# USB_PCIe.net
KiCad netlist of a schematic drawn in Altium Designer
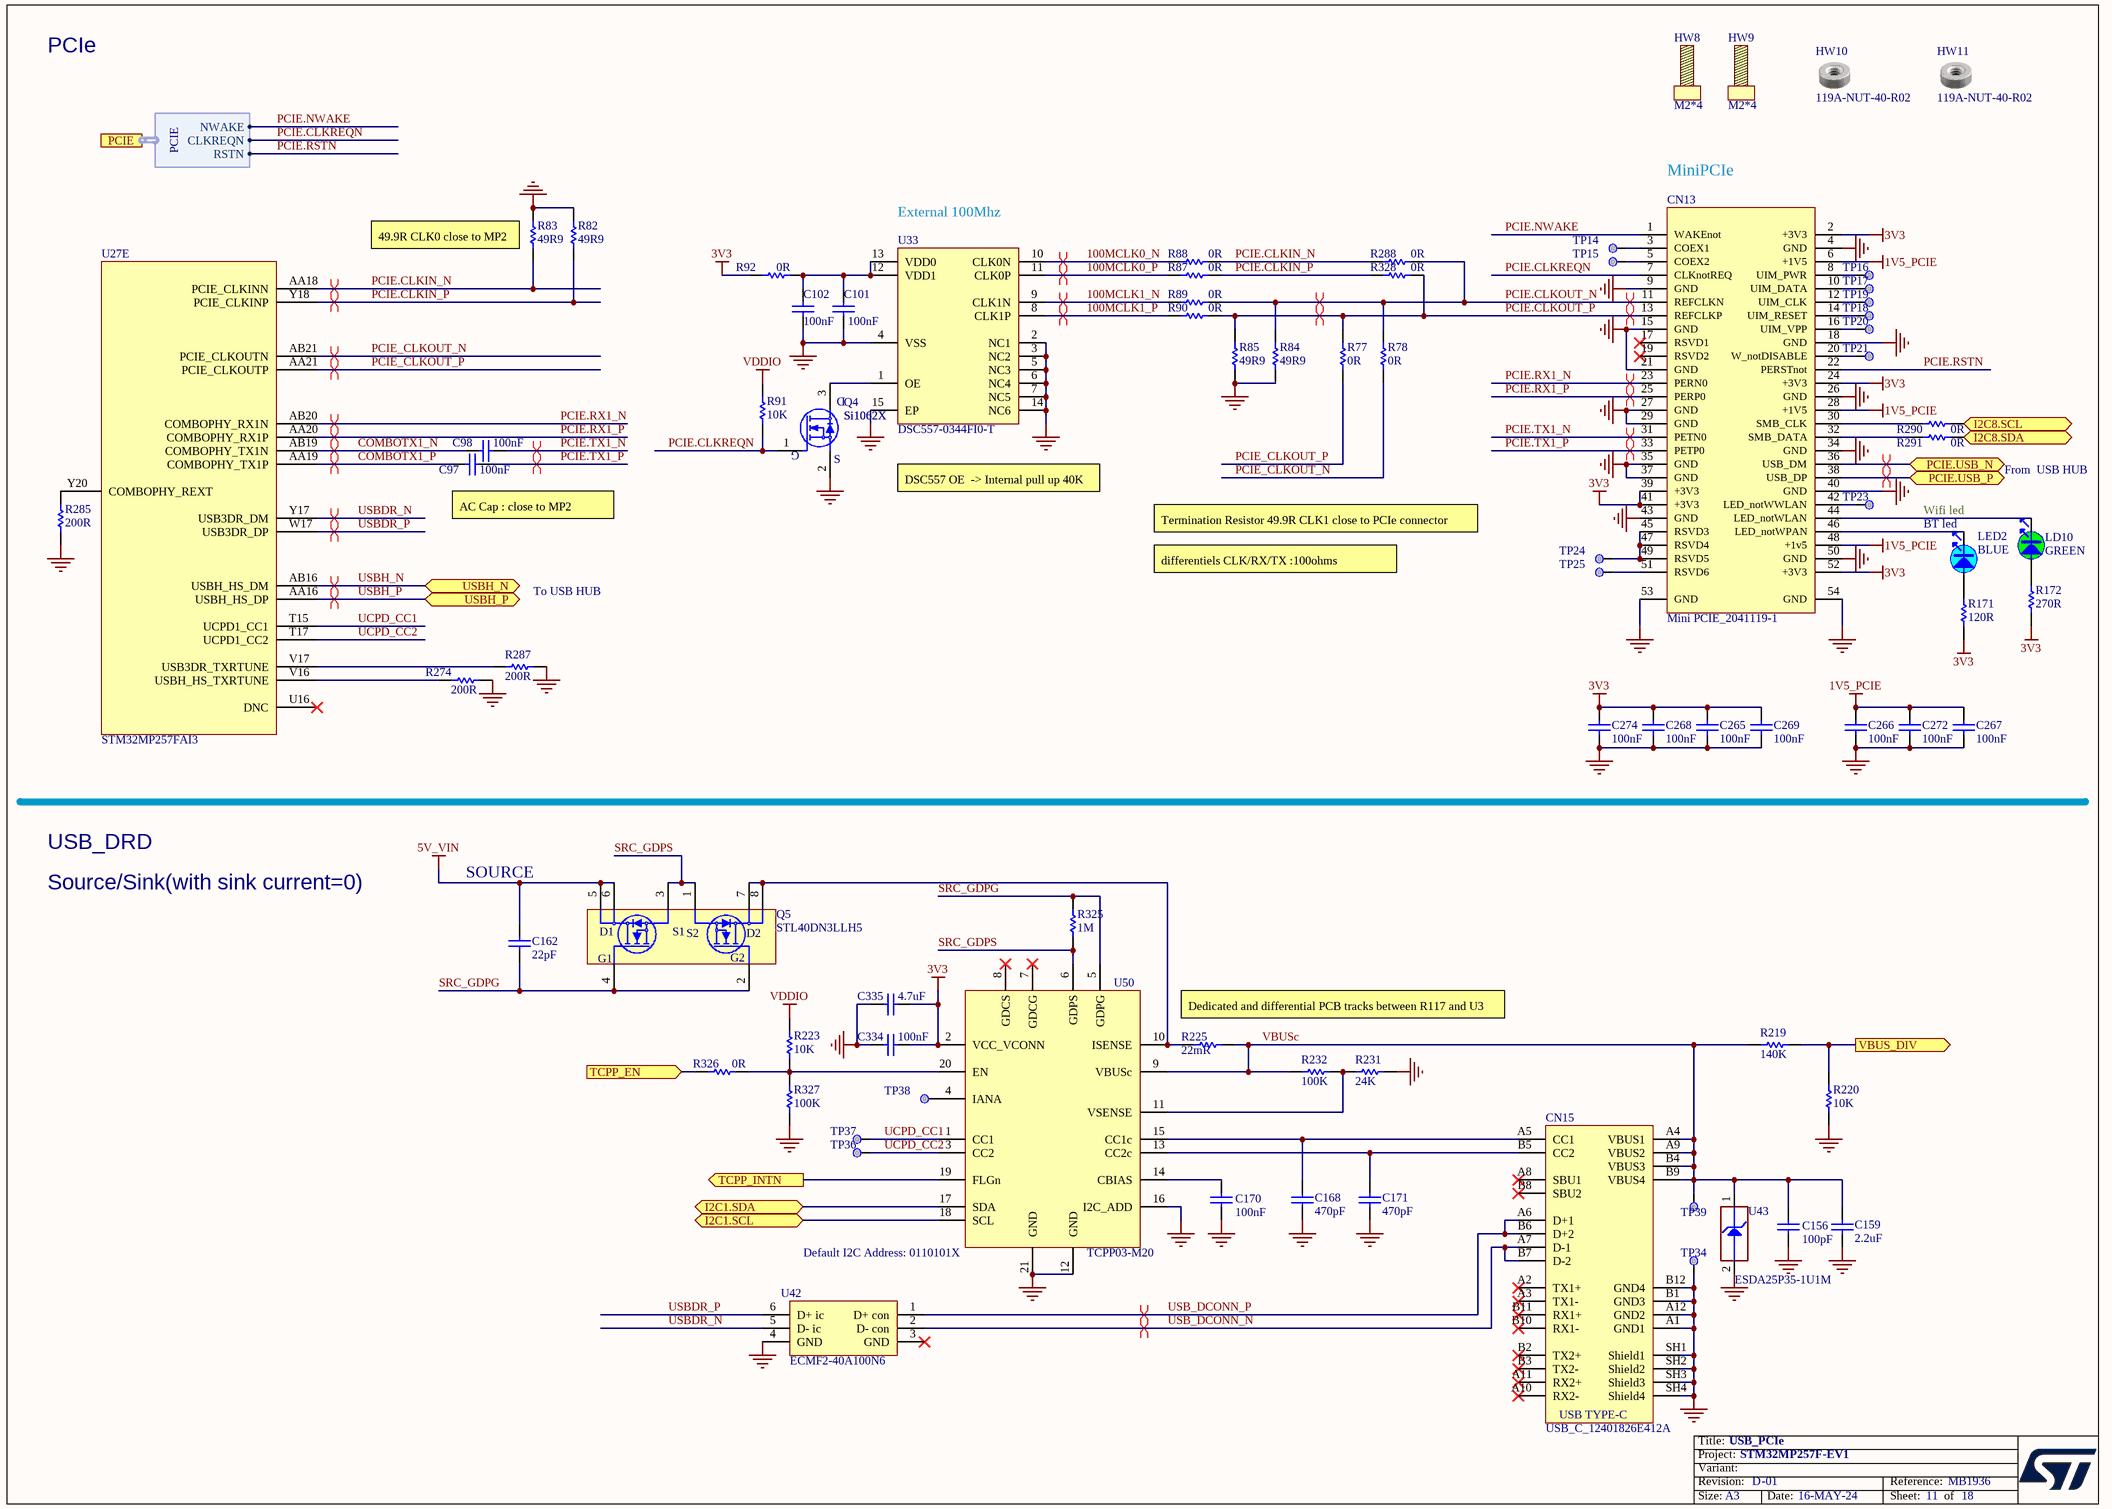
[diagram p0: USB_PCIe.SchDoc]

(export (version "E")
  (design (tool "Eeschema 10.0.6"))
  (components
    (comp (ref "C97")
      (value "100nF")
      (footprint "MCD_PARTS:C0201_MURATA_GRM033_H0P3")
      (description "Capacitor, MLCC,100nF, 10V, X7R, +/-10%, 0201, T=0.3mm")
      (fields (field (name "INTERNAL_PART_NUMBER") "MCD-01535") (field (name "MANUFACTURER") "MURATA"))
      (libsource (lib "MCD_PARTS_database") (part "Capacitor"))
    )
    (comp (ref "C98")
      (value "100nF")
      (footprint "MCD_PARTS:C0201_MURATA_GRM033_H0P3")
      (description "Capacitor, MLCC,100nF, 10V, X7R, +/-10%, 0201, T=0.3mm")
      (fields (field (name "INTERNAL_PART_NUMBER") "MCD-01535") (field (name "MANUFACTURER") "MURATA"))
      (libsource (lib "MCD_PARTS_database") (part "Capacitor"))
    )
    (comp (ref "C101")
      (value "100nF")
      (footprint "MCD_PARTS:C0402")
      (description "Capacitor, MLCC, 100nF, 16V, X7R, +/-10%, 0402, T=0.5mm")
      (fields (field (name "INTERNAL_PART_NUMBER") "MCD-00006") (field (name "MANUFACTURER") "YAGEO"))
      (libsource (lib "MCD_PARTS_database") (part "Capacitor"))
    )
    (comp (ref "C102")
      (value "100nF")
      (footprint "MCD_PARTS:C0402")
      (description "Capacitor, MLCC, 100nF, 16V, X7R, +/-10%, 0402, T=0.5mm")
      (fields (field (name "INTERNAL_PART_NUMBER") "MCD-00006") (field (name "MANUFACTURER") "YAGEO"))
      (libsource (lib "MCD_PARTS_database") (part "Capacitor"))
    )
    (comp (ref "C156")
      (value "100pF")
      (footprint "MCD_PARTS:C0402")
      (description "Capacitor, MLCC, 100pF, 50V, NPO, +/-5%, 0402, T=0.5mm")
      (fields
        (field (name "INTERNAL_PART_NUMBER") "MCD-00205")
        (field (name "MANUFACTURER_PART_NUMBER") "CC0402JRNPO9BN101")
      )
      (libsource (lib "MCD_PARTS_database") (part "Capacitor"))
    )
    (comp (ref "C159")
      (value "2.2uF")
      (footprint "MCD_PARTS:C0805")
      (description "Capacitor, MLCC, 2.2uF, 25V, X7R, +/-10%, 0805, T=1,25mm")
      (fields (field (name "INTERNAL_PART_NUMBER") "MCD-02372") (field (name "MANUFACTURER") "MURATA"))
      (libsource (lib "MCD_PARTS_database") (part "Capacitor"))
    )
    (comp (ref "C162")
      (value "22pF")
      (footprint "MCD_PARTS:C0402")
      (description "Capacitor, MLCC, 22pF, 50V, C0G, +/-5%, 0402, T=0.5mm")
      (fields (field (name "INTERNAL_PART_NUMBER") "MCD-01995") (field (name "MANUFACTURER") "TDK"))
      (libsource (lib "MCD_PARTS_database") (part "Capacitor"))
    )
    (comp (ref "C168")
      (value "470pF")
      (footprint "MCD_PARTS:C0402")
      (description "Capacitor, MLCC, 470pF, 50V, NPO, +/-5%, 0402, T=0.5mm")
      (fields
        (field (name "INTERNAL_PART_NUMBER") "MCD-00724")
        (field (name "MANUFACTURER_PART_NUMBER") "CC0402JRNPO9BN471")
      )
      (libsource (lib "MCD_PARTS_database") (part "Capacitor"))
    )
    (comp (ref "C170")
      (value "100nF")
      (footprint "MCD_PARTS:C0603")
      (description "Capacitor, MLCC, 100nF, 50V, X7R, +/-10%, 0603, T=0.8mm")
      (fields (field (name "INTERNAL_PART_NUMBER") "MCD-01099") (field (name "BMS_PART_NUMBER") "9142278"))
      (libsource (lib "MCD_PARTS_database") (part "Capacitor"))
    )
    (comp (ref "C171")
      (value "470pF")
      (footprint "MCD_PARTS:C0402")
      (description "Capacitor, MLCC, 470pF, 50V, NPO, +/-5%, 0402, T=0.5mm")
      (fields
        (field (name "INTERNAL_PART_NUMBER") "MCD-00724")
        (field (name "MANUFACTURER_PART_NUMBER") "CC0402JRNPO9BN471")
      )
      (libsource (lib "MCD_PARTS_database") (part "Capacitor"))
    )
    (comp (ref "C265")
      (value "100nF")
      (footprint "MCD_PARTS:C0201_H0P3")
      (description "Capacitor, MLCC, 100nF,10V, X5R, +/-10%, 0201, T=0.3mm")
      (fields
        (field (name "INTERNAL_PART_NUMBER") "MCD-00697")
        (field (name "MANUFACTURER_PART_NUMBER") "C0603X5R1A104K030BC")
      )
      (libsource (lib "MCD_PARTS_database") (part "Capacitor"))
    )
    (comp (ref "C266")
      (value "100nF")
      (footprint "MCD_PARTS:C0201_H0P3")
      (description "Capacitor, MLCC, 100nF,10V, X5R, +/-10%, 0201, T=0.3mm")
      (fields
        (field (name "INTERNAL_PART_NUMBER") "MCD-00697")
        (field (name "MANUFACTURER_PART_NUMBER") "C0603X5R1A104K030BC")
      )
      (libsource (lib "MCD_PARTS_database") (part "Capacitor"))
    )
    (comp (ref "C267")
      (value "100nF")
      (footprint "MCD_PARTS:C0201_H0P3")
      (description "Capacitor, MLCC, 100nF,10V, X5R, +/-10%, 0201, T=0.3mm")
      (fields
        (field (name "INTERNAL_PART_NUMBER") "MCD-00697")
        (field (name "MANUFACTURER_PART_NUMBER") "C0603X5R1A104K030BC")
      )
      (libsource (lib "MCD_PARTS_database") (part "Capacitor"))
    )
    (comp (ref "C268")
      (value "100nF")
      (footprint "MCD_PARTS:C0201_H0P3")
      (description "Capacitor, MLCC, 100nF,10V, X5R, +/-10%, 0201, T=0.3mm")
      (fields
        (field (name "INTERNAL_PART_NUMBER") "MCD-00697")
        (field (name "MANUFACTURER_PART_NUMBER") "C0603X5R1A104K030BC")
      )
      (libsource (lib "MCD_PARTS_database") (part "Capacitor"))
    )
    (comp (ref "C269")
      (value "100nF")
      (footprint "MCD_PARTS:C0201_H0P3")
      (description "Capacitor, MLCC, 100nF,10V, X5R, +/-10%, 0201, T=0.3mm")
      (fields
        (field (name "INTERNAL_PART_NUMBER") "MCD-00697")
        (field (name "MANUFACTURER_PART_NUMBER") "C0603X5R1A104K030BC")
      )
      (libsource (lib "MCD_PARTS_database") (part "Capacitor"))
    )
    (comp (ref "C272")
      (value "100nF")
      (footprint "MCD_PARTS:C0201_H0P3")
      (description "Capacitor, MLCC, 100nF,10V, X5R, +/-10%, 0201, T=0.3mm")
      (fields
        (field (name "INTERNAL_PART_NUMBER") "MCD-00697")
        (field (name "MANUFACTURER_PART_NUMBER") "C0603X5R1A104K030BC")
      )
      (libsource (lib "MCD_PARTS_database") (part "Capacitor"))
    )
    (comp (ref "C274")
      (value "100nF")
      (footprint "MCD_PARTS:C0201_H0P3")
      (description "Capacitor, MLCC, 100nF,10V, X5R, +/-10%, 0201, T=0.3mm")
      (fields
        (field (name "INTERNAL_PART_NUMBER") "MCD-00697")
        (field (name "MANUFACTURER_PART_NUMBER") "C0603X5R1A104K030BC")
      )
      (libsource (lib "MCD_PARTS_database") (part "Capacitor"))
    )
    (comp (ref "C334")
      (value "100nF")
      (footprint "MCD_PARTS:C0402")
      (description "Capacitor, MLCC, 100nF, 16V, X7R, +/-10%, 0402, T=0.5mm")
      (fields (field (name "INTERNAL_PART_NUMBER") "MCD-00006") (field (name "MANUFACTURER") "YAGEO"))
      (libsource (lib "MCD_PARTS_database") (part "Capacitor"))
    )
    (comp (ref "C335")
      (value "4.7uF")
      (footprint "MCD_PARTS:C0402")
      (description "Capacitor, MLCC, 4.7uF, 6V3, X5R, +/-20%, 0402, T=0.5mm")
      (fields (field (name "INTERNAL_PART_NUMBER") "MCD-01356") (field (name "MANUFACTURER") "MURATA"))
      (libsource (lib "MCD_PARTS_database") (part "Capacitor"))
    )
    (comp (ref "CN13")
      (value "Mini PCIE_2041119-1")
      (footprint "MCD_PARTS:CON_TE-CONNECTIVITY_2041119-1_HALF-CARD")
      (description "Socket_Mini PCIE, 52 pins, RA, SMD, T=4mm")
      (fields
        (field (name "INTERNAL_PART_NUMBER") "MCD-02227")
        (field (name "MANUFACTURER") "TE CONNECTIVITY")
      )
      (libsource (lib "MCD_PARTS_database") (part "SOCKET_Mini_PCIE"))
    )
    (comp (ref "CN15")
      (value "USB_C_12401826E412A")
      (footprint "MCD_PARTS:CON_USB-TYPEC_AMPHENOL_12401826E412A")
      (description "USB_TypeC, 24 pins, RA, SMD, T=2.96mm")
      (fields (field (name "INTERNAL_PART_NUMBER") "MCD-03232") (field (name "MANUFACTURER") "AMPHENOL ICC"))
      (libsource (lib "MCD_PARTS_database") (part "USB_TYPE_C_Receptacle"))
    )
    (comp (ref "HW8")
      (value "M2*4")
      (description "Screw , M2*4 mm")
      (fields (field (name "INTERNAL_PART_NUMBER") "MCD-02934") (field (name "MANUFACTURER") "RS PRO"))
      (libsource (lib "MCD_PARTS_database") (part "SCREW"))
    )
    (comp (ref "HW9")
      (value "M2*4")
      (description "Screw , M2*4 mm")
      (fields (field (name "INTERNAL_PART_NUMBER") "MCD-02934") (field (name "MANUFACTURER") "RS PRO"))
      (libsource (lib "MCD_PARTS_database") (part "SCREW"))
    )
    (comp (ref "HW10")
      (value "119A-NUT-40-R02")
      (footprint "MCD_PARTS:MISC_119A-NUT-40-R02")
      (description "MiniPCIe Stand off , 1.6mm")
      (fields (field (name "INTERNAL_PART_NUMBER") "MCD-03022") (field (name "MANUFACTURER") "ATTEND"))
      (libsource (lib "MCD_PARTS_database") (part "Standoff_mini_PCIE"))
    )
    (comp (ref "HW11")
      (value "119A-NUT-40-R02")
      (footprint "MCD_PARTS:MISC_119A-NUT-40-R02")
      (description "MiniPCIe Stand off , 1.6mm")
      (fields (field (name "INTERNAL_PART_NUMBER") "MCD-03022") (field (name "MANUFACTURER") "ATTEND"))
      (libsource (lib "MCD_PARTS_database") (part "Standoff_mini_PCIE"))
    )
    (comp (ref "LD10")
      (value "GREEN")
      (footprint "MCD_PARTS:LED_0603_OSRAM_LG-Q396-PS-35_GREEN_1A2K_H0P4")
      (description "LED Green, 0603 SMD, Forward Voltage Typ=2V, Max=2.5V")
      (fields
        (field (name "INTERNAL_PART_NUMBER") "MCD-00588")
        (field (name "MANUFACTURER_PART_NUMBER") "LG Q396-PS-35")
        (field (name "PROVIDED_BY") "SUBCO")
      )
      (libsource (lib "MCD_PARTS_database") (part "LED_green"))
    )
    (comp (ref "LED2")
      (value "BLUE")
      (footprint "MCD_PARTS:LED_0603_OSRAM_LB-Q39G-L2OO-35-1_BLUE_1A2K_H0P4")
      (description "LED Blue, 0603 SMD, Forward Voltage Min=2,8V, Max=3,8V")
      (fields
        (field (name "INTERNAL_PART_NUMBER") "MCD-00585")
        (field (name "MANUFACTURER_PART_NUMBER") "LB Q39G-L2OO-35-1")
        (field (name "PROVIDED_BY") "SUBCO")
      )
      (libsource (lib "MCD_PARTS_database") (part "LED_blue"))
    )
    (comp (ref "Q4")
      (value "Si1062X")
      (footprint "MCD_PARTS:MOS_SC89-3L")
      (description "MOSFET N-CH 20V SC-89")
      (fields
        (field (name "INTERNAL_PART_NUMBER") "MCD-02221")
        (field (name "MANUFACTURER") "VISHAY")
        (field (name "MANUFACTURER_PART_NUMBER") "Si1062X")
      )
      (libsource (lib "MCD_PARTS_database") (part "MOSFET_N-CHANNEL"))
    )
    (comp (ref "Q5")
      (value "STL40DN3LLH5")
      (footprint "MCD_PARTS:PowerFLAT_5x6")
      (description "MOSFET, Dual N-channel 30 V, 0.016 Ω typ., 40 A, STripFET™ H5 Power MOSFET")
      (fields
        (field (name "INTERNAL_PART_NUMBER") "MCD-02152")
        (field (name "MANUFACTURER") "STMICROELECTRONICS")
      )
      (libsource (lib "MCD_PARTS_database") (part "STL40DN3LLH5"))
    )
    (comp (ref "R77")
      (value "0R")
      (footprint "MCD_PARTS:R0402")
      (description "Resistor, 0R, 0402, +/-5%, 1/16W")
      (fields (field (name "INTERNAL_PART_NUMBER") "MCD-00052") (field (name "MANUFACTURER") "YAGEO"))
      (libsource (lib "MCD_PARTS_database") (part "Resistor"))
    )
    (comp (ref "R78")
      (value "0R")
      (footprint "MCD_PARTS:R0402")
      (description "Resistor, 0R, 0402, +/-5%, 1/16W")
      (fields (field (name "INTERNAL_PART_NUMBER") "MCD-00052") (field (name "MANUFACTURER") "YAGEO"))
      (libsource (lib "MCD_PARTS_database") (part "Resistor"))
    )
    (comp (ref "R82")
      (value "49R9")
      (footprint "MCD_PARTS:R0402")
      (description "Resistor, 49R9, 0402, +/-1%, 1/16W")
      (fields (field (name "INTERNAL_PART_NUMBER") "MCD-00565") (field (name "MANUFACTURER") "YAGEO"))
      (libsource (lib "MCD_PARTS_database") (part "Resistor"))
    )
    (comp (ref "R83")
      (value "49R9")
      (footprint "MCD_PARTS:R0402")
      (description "Resistor, 49R9, 0402, +/-1%, 1/16W")
      (fields (field (name "INTERNAL_PART_NUMBER") "MCD-00565") (field (name "MANUFACTURER") "YAGEO"))
      (libsource (lib "MCD_PARTS_database") (part "Resistor"))
    )
    (comp (ref "R84")
      (value "49R9")
      (footprint "MCD_PARTS:R0402")
      (description "Resistor, 49R9, 0402, +/-1%, 1/16W")
      (fields (field (name "INTERNAL_PART_NUMBER") "MCD-00565") (field (name "MANUFACTURER") "YAGEO"))
      (libsource (lib "MCD_PARTS_database") (part "Resistor"))
    )
    (comp (ref "R85")
      (value "49R9")
      (footprint "MCD_PARTS:R0402")
      (description "Resistor, 49R9, 0402, +/-1%, 1/16W")
      (fields (field (name "INTERNAL_PART_NUMBER") "MCD-00565") (field (name "MANUFACTURER") "YAGEO"))
      (libsource (lib "MCD_PARTS_database") (part "Resistor"))
    )
    (comp (ref "R87")
      (value "0R")
      (footprint "MCD_PARTS:R0402")
      (description "Resistor, 0R, 0402, +/-5%, 1/16W")
      (fields (field (name "INTERNAL_PART_NUMBER") "MCD-00052") (field (name "MANUFACTURER") "YAGEO"))
      (libsource (lib "MCD_PARTS_database") (part "Resistor"))
    )
    (comp (ref "R88")
      (value "0R")
      (footprint "MCD_PARTS:R0402")
      (description "Resistor, 0R, 0402, +/-5%, 1/16W")
      (fields (field (name "INTERNAL_PART_NUMBER") "MCD-00052") (field (name "MANUFACTURER") "YAGEO"))
      (libsource (lib "MCD_PARTS_database") (part "Resistor"))
    )
    (comp (ref "R89")
      (value "0R")
      (footprint "MCD_PARTS:R0402")
      (description "Resistor, 0R, 0402, +/-5%, 1/16W")
      (fields (field (name "INTERNAL_PART_NUMBER") "MCD-00052") (field (name "MANUFACTURER") "YAGEO"))
      (libsource (lib "MCD_PARTS_database") (part "Resistor"))
    )
    (comp (ref "R90")
      (value "0R")
      (footprint "MCD_PARTS:R0402")
      (description "Resistor, 0R, 0402, +/-5%, 1/16W")
      (fields (field (name "INTERNAL_PART_NUMBER") "MCD-00052") (field (name "MANUFACTURER") "YAGEO"))
      (libsource (lib "MCD_PARTS_database") (part "Resistor"))
    )
    (comp (ref "R91")
      (value "10K")
      (footprint "MCD_PARTS:R0402")
      (description "Resistor, 10K, 0402, +/-1%, 1/16W")
      (fields (field (name "INTERNAL_PART_NUMBER") "MCD-00053") (field (name "BMS_PART_NUMBER") "9131590"))
      (libsource (lib "MCD_PARTS_database") (part "Resistor"))
    )
    (comp (ref "R92")
      (value "0R")
      (footprint "MCD_PARTS:R0402")
      (description "Resistor, 0R, 0402, +/-5%, 1/16W")
      (fields (field (name "INTERNAL_PART_NUMBER") "MCD-00052") (field (name "MANUFACTURER") "YAGEO"))
      (libsource (lib "MCD_PARTS_database") (part "Resistor"))
    )
    (comp (ref "R171")
      (value "120R")
      (footprint "MCD_PARTS:R0402")
      (description "Resistor,120R,0402,1%,1/16W")
      (fields
        (field (name "INTERNAL_PART_NUMBER") "MCD-00194")
        (field (name "MANUFACTURER_PART_NUMBER") "RC0402FR-07120RL")
        (field (name "PROVIDED_BY") "SUBCO")
      )
      (libsource (lib "MCD_PARTS_database") (part "Resistor"))
    )
    (comp (ref "R172")
      (value "270R")
      (footprint "MCD_PARTS:R0402")
      (description "Resistor,270R,0402,1%,1/16W")
      (fields
        (field (name "INTERNAL_PART_NUMBER") "MCD-00441")
        (field (name "MANUFACTURER_PART_NUMBER") "RC0402FR-07270RL")
        (field (name "PROVIDED_BY") "SUBCO")
      )
      (libsource (lib "MCD_PARTS_database") (part "Resistor"))
    )
    (comp (ref "R219")
      (value "140K")
      (footprint "MCD_PARTS:R0402")
      (description "Resistor, 140K, 0402, +/-1%, 1/16W")
      (fields (field (name "INTERNAL_PART_NUMBER") "MCD-02335") (field (name "MANUFACTURER") "YAGEO"))
      (libsource (lib "MCD_PARTS_database") (part "Resistor"))
    )
    (comp (ref "R220")
      (value "10K")
      (footprint "MCD_PARTS:R0402")
      (description "Resistor, 10K, 0402, +/-1%, 1/16W")
      (fields (field (name "INTERNAL_PART_NUMBER") "MCD-00053") (field (name "BMS_PART_NUMBER") "9131590"))
      (libsource (lib "MCD_PARTS_database") (part "Resistor"))
    )
    (comp (ref "R223")
      (value "10K")
      (footprint "MCD_PARTS:R0402")
      (description "Resistor, 10K, 0402, +/-1%, 1/16W")
      (fields (field (name "INTERNAL_PART_NUMBER") "MCD-00053") (field (name "BMS_PART_NUMBER") "9131590"))
      (libsource (lib "MCD_PARTS_database") (part "Resistor"))
    )
    (comp (ref "R225")
      (value "22mR")
      (footprint "MCD_PARTS:R0603")
      (description "Resistor, 22mR, 0603, +/-1%, 1/3W")
      (fields (field (name "INTERNAL_PART_NUMBER") "MCD-02232") (field (name "MANUFACTURER") "PANASONIC"))
      (libsource (lib "MCD_PARTS_database") (part "Resistor"))
    )
    (comp (ref "R231")
      (value "24K")
      (footprint "MCD_PARTS:R0402")
      (description "Resistor, 24K, 0402, +/-1%, 1/16W")
      (fields (field (name "INTERNAL_PART_NUMBER") "MCD-00435") (field (name "MANUFACTURER") "YAGEO"))
      (libsource (lib "MCD_PARTS_database") (part "Resistor"))
    )
    (comp (ref "R232")
      (value "100K")
      (footprint "MCD_PARTS:R0402")
      (description "Resistor,100K,0402,0.5%,1/16W")
      (fields (field (name "INTERNAL_PART_NUMBER") "MCD-02265") (field (name "MANUFACTURER") "YAGEO"))
      (libsource (lib "MCD_PARTS_database") (part "Resistor"))
    )
    (comp (ref "R274")
      (value "200R")
      (footprint "MCD_PARTS:R0402")
      (description "Resistor, 200R, 0402, +/-1%, 1/16W")
      (fields (field (name "INTERNAL_PART_NUMBER") "MCD-00417") (field (name "MANUFACTURER") "YAGEO"))
      (libsource (lib "MCD_PARTS_database") (part "Resistor"))
    )
    (comp (ref "R285")
      (value "200R")
      (footprint "MCD_PARTS:R0402")
      (description "Resistor, 200R, 0402, +/-1%, 1/16W")
      (fields (field (name "INTERNAL_PART_NUMBER") "MCD-00417") (field (name "MANUFACTURER") "YAGEO"))
      (libsource (lib "MCD_PARTS_database") (part "Resistor"))
    )
    (comp (ref "R287")
      (value "200R")
      (footprint "MCD_PARTS:R0402")
      (description "Resistor, 200R, 0402, +/-1%, 1/16W")
      (fields (field (name "INTERNAL_PART_NUMBER") "MCD-00417") (field (name "MANUFACTURER") "YAGEO"))
      (libsource (lib "MCD_PARTS_database") (part "Resistor"))
    )
    (comp (ref "R288")
      (value "0R")
      (footprint "MCD_PARTS:R0402")
      (description "Resistor,0R,0402,5%,1/16W")
      (fields (field (name "INTERNAL_PART_NUMBER") "MCD-00052") (field (name "MANUFACTURER") "YAGEO"))
      (libsource (lib "MCD_PARTS_database") (part "Resistor"))
    )
    (comp (ref "R290")
      (value "0R")
      (footprint "MCD_PARTS:R0402")
      (description "Resistor, 0R, 0402, +/-5%, 1/16W")
      (fields (field (name "INTERNAL_PART_NUMBER") "MCD-00052") (field (name "MANUFACTURER") "YAGEO"))
      (libsource (lib "MCD_PARTS_database") (part "Resistor"))
    )
    (comp (ref "R291")
      (value "0R")
      (footprint "MCD_PARTS:R0402")
      (description "Resistor, 0R, 0402, +/-5%, 1/16W")
      (fields (field (name "INTERNAL_PART_NUMBER") "MCD-00052") (field (name "MANUFACTURER") "YAGEO"))
      (libsource (lib "MCD_PARTS_database") (part "Resistor"))
    )
    (comp (ref "R325")
      (value "1M")
      (footprint "MCD_PARTS:R0402")
      (description "Resistor, 1M, 0402, +/-1%, 1/16W")
      (fields (field (name "INTERNAL_PART_NUMBER") "MCD-00182") (field (name "BMS_PART_NUMBER") "9131778"))
      (libsource (lib "MCD_PARTS_database") (part "Resistor"))
    )
    (comp (ref "R326")
      (value "0R")
      (footprint "MCD_PARTS:R0402")
      (description "Resistor,0R,0402,5%,1/16W")
      (fields
        (field (name "INTERNAL_PART_NUMBER") "MCD-00052")
        (field (name "MANUFACTURER_PART_NUMBER") "RC0402JR-070RL")
      )
      (libsource (lib "MCD_PARTS_database") (part "Resistor"))
    )
    (comp (ref "R327")
      (value "100K")
      (footprint "MCD_PARTS:R0402")
      (description "Resistor,100K,0402,0.5%,1/16W")
      (fields (field (name "INTERNAL_PART_NUMBER") "MCD-02265") (field (name "MANUFACTURER") "YAGEO"))
      (libsource (lib "MCD_PARTS_database") (part "Resistor"))
    )
    (comp (ref "R328")
      (value "0R")
      (footprint "MCD_PARTS:R0402")
      (description "Resistor,0R,0402,5%,1/16W")
      (fields (field (name "INTERNAL_PART_NUMBER") "MCD-00052") (field (name "MANUFACTURER") "YAGEO"))
      (libsource (lib "MCD_PARTS_database") (part "Resistor"))
    )
    (comp (ref "TP14")
      (value "Test Point")
      (footprint "MCD_PARTS:TP_SMD_1MM")
      (description "Test Point 1mm")
      (fields
        (field (name "INTERNAL_PART_NUMBER") "MCD-00074")
        (field (name "MANUFACTURER_PART_NUMBER") "n/a")
      )
      (libsource (lib "") (part "Test Point_1"))
    )
    (comp (ref "TP15")
      (value "Test Point")
      (footprint "MCD_PARTS:TP_SMD_1MM")
      (description "Test Point 1mm")
      (fields
        (field (name "INTERNAL_PART_NUMBER") "MCD-00074")
        (field (name "MANUFACTURER_PART_NUMBER") "n/a")
      )
      (libsource (lib "") (part "Test Point_1"))
    )
    (comp (ref "TP16")
      (value "Test Point")
      (footprint "MCD_PARTS:TP_SMD_1MM")
      (description "Test Point 1mm")
      (fields
        (field (name "INTERNAL_PART_NUMBER") "MCD-00074")
        (field (name "MANUFACTURER_PART_NUMBER") "n/a")
      )
      (libsource (lib "MCD_PARTS_database") (part "Test Point"))
    )
    (comp (ref "TP17")
      (value "Test Point")
      (footprint "MCD_PARTS:TP_SMD_1MM")
      (description "Test Point 1mm")
      (fields
        (field (name "INTERNAL_PART_NUMBER") "MCD-00074")
        (field (name "MANUFACTURER_PART_NUMBER") "n/a")
      )
      (libsource (lib "MCD_PARTS_database") (part "Test Point"))
    )
    (comp (ref "TP18")
      (value "Test Point")
      (footprint "MCD_PARTS:TP_SMD_1MM")
      (description "Test Point 1mm")
      (fields
        (field (name "INTERNAL_PART_NUMBER") "MCD-00074")
        (field (name "MANUFACTURER_PART_NUMBER") "n/a")
      )
      (libsource (lib "MCD_PARTS_database") (part "Test Point"))
    )
    (comp (ref "TP19")
      (value "Test Point")
      (footprint "MCD_PARTS:TP_SMD_1MM")
      (description "Test Point 1mm")
      (fields
        (field (name "INTERNAL_PART_NUMBER") "MCD-00074")
        (field (name "MANUFACTURER_PART_NUMBER") "n/a")
      )
      (libsource (lib "MCD_PARTS_database") (part "Test Point"))
    )
    (comp (ref "TP20")
      (value "Test Point")
      (footprint "MCD_PARTS:TP_SMD_1MM")
      (description "Test Point 1mm")
      (fields
        (field (name "INTERNAL_PART_NUMBER") "MCD-00074")
        (field (name "MANUFACTURER_PART_NUMBER") "n/a")
      )
      (libsource (lib "MCD_PARTS_database") (part "Test Point"))
    )
    (comp (ref "TP21")
      (value "Test Point")
      (footprint "MCD_PARTS:TP_SMD_1MM")
      (description "Test Point 1mm")
      (fields
        (field (name "INTERNAL_PART_NUMBER") "MCD-00074")
        (field (name "MANUFACTURER_PART_NUMBER") "n/a")
      )
      (libsource (lib "MCD_PARTS_database") (part "Test Point"))
    )
    (comp (ref "TP23")
      (value "Test Point")
      (footprint "MCD_PARTS:TP_SMD_1MM")
      (description "Test Point 1mm")
      (fields
        (field (name "INTERNAL_PART_NUMBER") "MCD-00074")
        (field (name "MANUFACTURER_PART_NUMBER") "n/a")
      )
      (libsource (lib "MCD_PARTS_database") (part "Test Point"))
    )
    (comp (ref "TP24")
      (value "Test Point")
      (footprint "MCD_PARTS:TP_SMD_1MM")
      (description "Test Point 1mm")
      (fields
        (field (name "INTERNAL_PART_NUMBER") "MCD-00074")
        (field (name "MANUFACTURER_PART_NUMBER") "n/a")
      )
      (libsource (lib "") (part "Test Point_1"))
    )
    (comp (ref "TP25")
      (value "Test Point")
      (footprint "MCD_PARTS:TP_SMD_1MM")
      (description "Test Point 1mm")
      (fields
        (field (name "INTERNAL_PART_NUMBER") "MCD-00074")
        (field (name "MANUFACTURER_PART_NUMBER") "n/a")
      )
      (libsource (lib "") (part "Test Point_1"))
    )
    (comp (ref "TP34")
      (value "Test Point")
      (footprint "MCD_PARTS:TP_SMD_1MM")
      (description "Test Point 1mm")
      (fields
        (field (name "INTERNAL_PART_NUMBER") "MCD-00074")
        (field (name "MANUFACTURER_PART_NUMBER") "n/a")
      )
      (libsource (lib "") (part "Test Point_2"))
    )
    (comp (ref "TP36")
      (value "Test Point")
      (footprint "MCD_PARTS:TP_SMD_1MM")
      (description "Test Point 1mm")
      (fields
        (field (name "INTERNAL_PART_NUMBER") "MCD-00074")
        (field (name "MANUFACTURER_PART_NUMBER") "n/a")
      )
      (libsource (lib "") (part "Test Point_1"))
    )
    (comp (ref "TP37")
      (value "Test Point")
      (footprint "MCD_PARTS:TP_SMD_1MM")
      (description "Test Point 1mm")
      (fields
        (field (name "INTERNAL_PART_NUMBER") "MCD-00074")
        (field (name "MANUFACTURER_PART_NUMBER") "n/a")
      )
      (libsource (lib "") (part "Test Point_1"))
    )
    (comp (ref "TP38")
      (value "Test Point")
      (footprint "MCD_PARTS:TP_SMD_1MM")
      (description "Test Point 1mm")
      (fields
        (field (name "INTERNAL_PART_NUMBER") "MCD-00074")
        (field (name "MANUFACTURER_PART_NUMBER") "n/a")
      )
      (libsource (lib "") (part "Test Point_1"))
    )
    (comp (ref "TP39")
      (value "Test Point")
      (footprint "MCD_PARTS:TP_SMD_1MM")
      (description "Test Point 1mm")
      (fields
        (field (name "INTERNAL_PART_NUMBER") "MCD-00074")
        (field (name "MANUFACTURER_PART_NUMBER") "n/a")
      )
      (libsource (lib "") (part "Test Point_3"))
    )
    (comp (ref "U27")
      (value "STM32MP257FAI3")
      (footprint "ICC_LFBGA436_18X18_P080_H1P70_STM32MP257_CODE-B0D1")
      (description "MPU, ARM Cortex-A35 + M33 32-bit MPU, 808KB RAM, With Crypto")
      (fields
        (field (name "INTERNAL_PART_NUMBER") "MCD-02000")
        (field (name "MANUFACTURER") "STMICROELECTRONICS")
      )
      (libsource (lib "MCD_PARTS_database") (part "STM32MP257FAI3"))
    )
    (comp (ref "U33")
      (value "DSC557-0344FI0-T")
      (footprint "MCD_PARTS:ICC_QFN14-EPAD_3P2X2P5_P050")
      (description "Crystal-less Two Output PCIe Gen1/2/3 Clock Generator 100Mhz , 2.25V to 3.6V, 100ppm")
      (fields (field (name "INTERNAL_PART_NUMBER") "MCD-02349") (field (name "MANUFACTURER") "MICROCHIP"))
      (libsource (lib "MCD_PARTS_database") (part "DSC557-0344FI0-T"))
    )
    (comp (ref "U42")
      (value "ECMF2-40A100N6")
      (footprint "MCD_PARTS:ESD_UQFN-6L_1P45X1P4_P040")
      (description "ESD protection & Common Filter High Speed serial Interfaces , 0.4 pitch")
      (fields
        (field (name "INTERNAL_PART_NUMBER") "MCD-03060")
        (field (name "MANUFACTURER") "STMICROELECTRONICS")
      )
      (libsource (lib "MCD_PARTS_database") (part "ECMF2-40A100N6"))
    )
    (comp (ref "U43")
      (value "ESDA25P35-1U1M")
      (footprint "MCD_PARTS:ESD_QFN1610_2N_1K_2A")
      (description "High power Transient voltage suppressor:25V/35A EOS and ESD transients protection.")
      (fields (field (name "INTERNAL_PART_NUMBER") "MCD-01207") (field (name "BMS_PART_NUMBER") "9179045"))
      (libsource (lib "MCD_PARTS_database") (part "ESD-TRANSIL"))
    )
    (comp (ref "U50")
      (value "TCPP03-M20")
      (footprint "MCD_PARTS:ICC_QFN20-EPAD_4X4_P050")
      (description "USB Type-C Port Protection for USB DRP Power Delivery, PPS compliant")
      (fields
        (field (name "INTERNAL_PART_NUMBER") "MCD-02130")
        (field (name "MANUFACTURER") "STMICROELECTRONICS")
      )
      (libsource (lib "MCD_PARTS_database") (part "TCPP03-M20"))
    )
  )
  (nets
    (net (code "2") (name "/100MCLK0_N") (class "Default")
      (node (ref "R88") (pin "1") (pinfunction "1_1") (pintype "passive"))
      (node (ref "U33") (pin "10") (pinfunction "CLK0N_10") (pintype "passive"))
    )
    (net (code "3") (name "/100MCLK0_P") (class "Default")
      (node (ref "R87") (pin "1") (pinfunction "1_1") (pintype "passive"))
      (node (ref "U33") (pin "11") (pinfunction "CLK0P_11") (pintype "passive"))
    )
    (net (code "4") (name "/100MCLK1_N") (class "Default")
      (node (ref "R89") (pin "1") (pinfunction "1_1") (pintype "passive"))
      (node (ref "U33") (pin "9") (pinfunction "CLK1N_9") (pintype "passive"))
    )
    (net (code "5") (name "/100MCLK1_P") (class "Default")
      (node (ref "R90") (pin "1") (pinfunction "1_1") (pintype "passive"))
      (node (ref "U33") (pin "8") (pinfunction "CLK1P_8") (pintype "passive"))
    )
    (net (code "6") (name "/COMBOTX1_N") (class "Default")
      (node (ref "C98") (pin "1") (pinfunction "1_1") (pintype "passive"))
      (node (ref "U27") (pin "AB19") (pinfunction "COMBOPHY_TX1N_AB19") (pintype "passive"))
    )
    (net (code "7") (name "/COMBOTX1_P") (class "Default")
      (node (ref "C97") (pin "1") (pinfunction "1_1") (pintype "passive"))
      (node (ref "U27") (pin "AA19") (pinfunction "COMBOPHY_TX1P_AA19") (pintype "passive"))
    )
    (net (code "8") (name "/I2C1.SCL") (class "Default")
      (node (ref "U50") (pin "18") (pinfunction "SCL_18") (pintype "passive"))
    )
    (net (code "9") (name "/I2C1.SDA") (class "Default")
      (node (ref "U50") (pin "17") (pinfunction "SDA_17") (pintype "passive"))
    )
    (net (code "10") (name "/I2C8.SCL") (class "Default")
      (node (ref "R290") (pin "2") (pinfunction "2_2") (pintype "passive"))
    )
    (net (code "11") (name "/I2C8.SDA") (class "Default")
      (node (ref "R291") (pin "2") (pinfunction "2_2") (pintype "passive"))
    )
    (net (code "12") (name "/PCIE.CLKIN_N") (class "Default")
      (node (ref "R288") (pin "2") (pinfunction "2_2") (pintype "passive"))
      (node (ref "R83") (pin "1") (pinfunction "1_1") (pintype "passive"))
      (node (ref "R88") (pin "2") (pinfunction "2_2") (pintype "passive"))
      (node (ref "U27") (pin "AA18") (pinfunction "PCIE_CLKINN_AA18") (pintype "passive"))
    )
    (net (code "13") (name "/PCIE.CLKIN_P") (class "Default")
      (node (ref "R328") (pin "2") (pinfunction "2_2") (pintype "passive"))
      (node (ref "R82") (pin "1") (pinfunction "1_1") (pintype "passive"))
      (node (ref "R87") (pin "2") (pinfunction "2_2") (pintype "passive"))
      (node (ref "U27") (pin "Y18") (pinfunction "PCIE_CLKINP_Y18") (pintype "passive"))
    )
    (net (code "14") (name "/PCIE.CLKOUT_N") (class "Default")
      (node (ref "CN13") (pin "11") (pinfunction "REFCLKN_11") (pintype "passive"))
      (node (ref "R288") (pin "1") (pinfunction "1_1") (pintype "passive"))
      (node (ref "R78") (pin "2") (pinfunction "2_2") (pintype "passive"))
      (node (ref "R84") (pin "2") (pinfunction "2_2") (pintype "passive"))
      (node (ref "R89") (pin "2") (pinfunction "2_2") (pintype "passive"))
    )
    (net (code "15") (name "/PCIE.CLKOUT_P") (class "Default")
      (node (ref "CN13") (pin "13") (pinfunction "REFCLKP_13") (pintype "passive"))
      (node (ref "R328") (pin "1") (pinfunction "1_1") (pintype "passive"))
      (node (ref "R77") (pin "2") (pinfunction "2_2") (pintype "passive"))
      (node (ref "R85") (pin "2") (pinfunction "2_2") (pintype "passive"))
      (node (ref "R90") (pin "2") (pinfunction "2_2") (pintype "passive"))
    )
    (net (code "16") (name "/PCIE.CLKREQN") (class "Default")
      (node (ref "CN13") (pin "7") (pinfunction "CLKnotREQ_7") (pintype "passive"))
      (node (ref "Q4") (pin "1") (pinfunction "G_1") (pintype "passive"))
      (node (ref "R91") (pin "1") (pinfunction "1_1") (pintype "passive"))
    )
    (net (code "17") (name "/PCIE.NWAKE") (class "Default")
      (node (ref "CN13") (pin "1") (pinfunction "WAKEnot_1") (pintype "passive"))
    )
    (net (code "18") (name "/PCIE.RSTN") (class "Default")
      (node (ref "CN13") (pin "22") (pinfunction "PERSTnot_22") (pintype "passive"))
    )
    (net (code "19") (name "/PCIE.RX1_N") (class "Default")
      (node (ref "CN13") (pin "23") (pinfunction "PERN0_23") (pintype "passive"))
      (node (ref "U27") (pin "AB20") (pinfunction "COMBOPHY_RX1N_AB20") (pintype "passive"))
    )
    (net (code "20") (name "/PCIE.RX1_P") (class "Default")
      (node (ref "CN13") (pin "25") (pinfunction "PERP0_25") (pintype "passive"))
      (node (ref "U27") (pin "AA20") (pinfunction "COMBOPHY_RX1P_AA20") (pintype "passive"))
    )
    (net (code "21") (name "/PCIE.TX1_N") (class "Default")
      (node (ref "C98") (pin "2") (pinfunction "2_2") (pintype "passive"))
      (node (ref "CN13") (pin "31") (pinfunction "PETN0_31") (pintype "passive"))
    )
    (net (code "22") (name "/PCIE.TX1_P") (class "Default")
      (node (ref "C97") (pin "2") (pinfunction "2_2") (pintype "passive"))
      (node (ref "CN13") (pin "33") (pinfunction "PETP0_33") (pintype "passive"))
    )
    (net (code "23") (name "/PCIE.USB_N") (class "Default")
      (node (ref "CN13") (pin "36") (pinfunction "USB_DM_36") (pintype "passive"))
    )
    (net (code "24") (name "/PCIE.USB_P") (class "Default")
      (node (ref "CN13") (pin "38") (pinfunction "USB_DP_38") (pintype "passive"))
    )
    (net (code "25") (name "/PCIE_CLKOUT_N") (class "Default")
      (node (ref "R78") (pin "1") (pinfunction "1_1") (pintype "passive"))
      (node (ref "U27") (pin "AB21") (pinfunction "PCIE_CLKOUTN_AB21") (pintype "passive"))
    )
    (net (code "26") (name "/PCIE_CLKOUT_P") (class "Default")
      (node (ref "R77") (pin "1") (pinfunction "1_1") (pintype "passive"))
      (node (ref "U27") (pin "AA21") (pinfunction "PCIE_CLKOUTP_AA21") (pintype "passive"))
    )
    (net (code "27") (name "/SRC_GDPG") (class "Default")
      (node (ref "C162") (pin "1") (pinfunction "1_1") (pintype "passive"))
      (node (ref "Q5") (pin "2") (pinfunction "G2_2") (pintype "passive"))
      (node (ref "Q5") (pin "4") (pinfunction "G1_4") (pintype "passive"))
      (node (ref "R325") (pin "2") (pinfunction "2_2") (pintype "passive"))
      (node (ref "U50") (pin "5") (pinfunction "GDPG_5") (pintype "passive"))
    )
    (net (code "28") (name "/SRC_GDPS") (class "Default")
      (node (ref "Q5") (pin "1") (pinfunction "S2_1") (pintype "passive"))
      (node (ref "Q5") (pin "3") (pinfunction "S1_3") (pintype "passive"))
      (node (ref "R325") (pin "1") (pinfunction "1_1") (pintype "passive"))
      (node (ref "U50") (pin "6") (pinfunction "GDPS_6") (pintype "passive"))
    )
    (net (code "29") (name "/TCPP_EN") (class "Default")
      (node (ref "R326") (pin "1") (pinfunction "1_1") (pintype "passive"))
    )
    (net (code "30") (name "/TCPP_INTN") (class "Default")
      (node (ref "U50") (pin "19") (pinfunction "FLGn_19") (pintype "passive"))
    )
    (net (code "31") (name "/UCPD_CC1") (class "Default")
      (node (ref "TP37") (pin "1") (pinfunction "1_1") (pintype "passive"))
      (node (ref "U27") (pin "T15") (pinfunction "UCPD1_CC1_T15") (pintype "passive"))
      (node (ref "U50") (pin "1") (pinfunction "CC1_1") (pintype "passive"))
    )
    (net (code "32") (name "/UCPD_CC2") (class "Default")
      (node (ref "TP36") (pin "1") (pinfunction "1_1") (pintype "passive"))
      (node (ref "U27") (pin "T17") (pinfunction "UCPD1_CC2_T17") (pintype "passive"))
      (node (ref "U50") (pin "3") (pinfunction "CC2_3") (pintype "passive"))
    )
    (net (code "33") (name "/USBDR_N") (class "Default")
      (node (ref "U27") (pin "Y17") (pinfunction "USB3DR_DM_Y17") (pintype "passive"))
      (node (ref "U42") (pin "5") (pinfunction "D-_ic_5") (pintype "passive"))
    )
    (net (code "34") (name "/USBDR_P") (class "Default")
      (node (ref "U27") (pin "W17") (pinfunction "USB3DR_DP_W17") (pintype "passive"))
      (node (ref "U42") (pin "6") (pinfunction "D+_ic_6") (pintype "passive"))
    )
    (net (code "35") (name "/USBH_N") (class "Default")
      (node (ref "U27") (pin "AB16") (pinfunction "USBH_HS_DM_AB16") (pintype "passive"))
    )
    (net (code "36") (name "/USBH_P") (class "Default")
      (node (ref "U27") (pin "AA16") (pinfunction "USBH_HS_DP_AA16") (pintype "passive"))
    )
    (net (code "37") (name "/USB_DCONN_N") (class "Default")
      (node (ref "CN15") (pin "A7") (pinfunction "D-1_A7") (pintype "passive"))
      (node (ref "CN15") (pin "B7") (pinfunction "D-2_B7") (pintype "passive"))
      (node (ref "U42") (pin "2") (pinfunction "D-_con_2") (pintype "passive"))
    )
    (net (code "38") (name "/USB_DCONN_P") (class "Default")
      (node (ref "CN15") (pin "A6") (pinfunction "D+1_A6") (pintype "passive"))
      (node (ref "CN15") (pin "B6") (pinfunction "D+2_B6") (pintype "passive"))
      (node (ref "U42") (pin "1") (pinfunction "D+_con_1") (pintype "passive"))
    )
    (net (code "39") (name "/VBUS_DIV") (class "Default")
      (node (ref "R219") (pin "1") (pinfunction "1_1") (pintype "passive"))
      (node (ref "R220") (pin "2") (pinfunction "2_2") (pintype "passive"))
    )
    (net (code "40") (name "/VBUSc") (class "Default")
      (node (ref "C156") (pin "2") (pinfunction "2_2") (pintype "passive"))
      (node (ref "C159") (pin "2") (pinfunction "2_2") (pintype "passive"))
      (node (ref "CN15") (pin "A4") (pinfunction "VBUS1_A4") (pintype "passive"))
      (node (ref "CN15") (pin "A9") (pinfunction "VBUS2_A9") (pintype "passive"))
      (node (ref "CN15") (pin "B4") (pinfunction "VBUS3_B4") (pintype "passive"))
      (node (ref "CN15") (pin "B9") (pinfunction "VBUS4_B9") (pintype "passive"))
      (node (ref "R219") (pin "2") (pinfunction "2_2") (pintype "passive"))
      (node (ref "R225") (pin "1") (pinfunction "1_1") (pintype "passive"))
      (node (ref "R232") (pin "1") (pinfunction "1_1") (pintype "passive"))
      (node (ref "TP39") (pin "1") (pinfunction "1_1") (pintype "passive"))
      (node (ref "U43") (pin "1") (pinfunction "IO1_1") (pintype "passive"))
      (node (ref "U50") (pin "9") (pinfunction "VBUSc_9") (pintype "passive"))
    )
    (net (code "42") (name "1V5_PCIE") (class "Default")
      (node (ref "C266") (pin "1") (pinfunction "1_1") (pintype "passive"))
      (node (ref "C267") (pin "1") (pinfunction "1_1") (pintype "passive"))
      (node (ref "C272") (pin "1") (pinfunction "1_1") (pintype "passive"))
      (node (ref "CN13") (pin "28") (pinfunction "+1V5_28") (pintype "passive"))
      (node (ref "CN13") (pin "48") (pinfunction "+1v5_48") (pintype "passive"))
      (node (ref "CN13") (pin "6") (pinfunction "+1V5_6") (pintype "passive"))
    )
    (net (code "43") (name "3V3") (class "Default")
      (node (ref "C265") (pin "1") (pinfunction "1_1") (pintype "passive"))
      (node (ref "C268") (pin "1") (pinfunction "1_1") (pintype "passive"))
      (node (ref "C269") (pin "2") (pinfunction "2_2") (pintype "passive"))
      (node (ref "C274") (pin "1") (pinfunction "1_1") (pintype "passive"))
      (node (ref "C334") (pin "1") (pinfunction "1_1") (pintype "passive"))
      (node (ref "C335") (pin "1") (pinfunction "1_1") (pintype "passive"))
      (node (ref "CN13") (pin "2") (pinfunction "+3V3_2") (pintype "passive"))
      (node (ref "CN13") (pin "24") (pinfunction "+3V3_24") (pintype "passive"))
      (node (ref "CN13") (pin "39") (pinfunction "+3V3_39") (pintype "passive"))
      (node (ref "CN13") (pin "41") (pinfunction "+3V3_41") (pintype "passive"))
      (node (ref "CN13") (pin "52") (pinfunction "+3V3_52") (pintype "passive"))
      (node (ref "R171") (pin "2") (pinfunction "2_2") (pintype "passive"))
      (node (ref "R172") (pin "1") (pinfunction "1_1") (pintype "passive"))
      (node (ref "R92") (pin "1") (pinfunction "1_1") (pintype "passive"))
      (node (ref "U50") (pin "2") (pinfunction "VCC_VCONN_2") (pintype "passive"))
    )
    (net (code "44") (name "5V_VIN") (class "Default")
      (node (ref "C162") (pin "2") (pinfunction "2_2") (pintype "passive"))
      (node (ref "Q5") (pin "5") (pinfunction "D1_5") (pintype "passive"))
      (node (ref "Q5") (pin "6") (pinfunction "D1_6") (pintype "passive"))
    )
    (net (code "45") (name "GND") (class "Default")
      (node (ref "C101") (pin "1") (pinfunction "1_1") (pintype "passive"))
      (node (ref "C102") (pin "1") (pinfunction "1_1") (pintype "passive"))
      (node (ref "C156") (pin "1") (pinfunction "1_1") (pintype "passive"))
      (node (ref "C159") (pin "1") (pinfunction "1_1") (pintype "passive"))
      (node (ref "C168") (pin "1") (pinfunction "1_1") (pintype "passive"))
      (node (ref "C170") (pin "1") (pinfunction "1_1") (pintype "passive"))
      (node (ref "C171") (pin "1") (pinfunction "1_1") (pintype "passive"))
      (node (ref "C265") (pin "2") (pinfunction "2_2") (pintype "passive"))
      (node (ref "C266") (pin "2") (pinfunction "2_2") (pintype "passive"))
      (node (ref "C267") (pin "2") (pinfunction "2_2") (pintype "passive"))
      (node (ref "C268") (pin "2") (pinfunction "2_2") (pintype "passive"))
      (node (ref "C269") (pin "1") (pinfunction "1_1") (pintype "passive"))
      (node (ref "C272") (pin "2") (pinfunction "2_2") (pintype "passive"))
      (node (ref "C274") (pin "2") (pinfunction "2_2") (pintype "passive"))
      (node (ref "C334") (pin "2") (pinfunction "2_2") (pintype "passive"))
      (node (ref "C335") (pin "2") (pinfunction "2_2") (pintype "passive"))
      (node (ref "CN13") (pin "15") (pinfunction "GND_15") (pintype "passive"))
      (node (ref "CN13") (pin "18") (pinfunction "GND_18") (pintype "passive"))
      (node (ref "CN13") (pin "21") (pinfunction "GND_21") (pintype "passive"))
      (node (ref "CN13") (pin "26") (pinfunction "GND_26") (pintype "passive"))
      (node (ref "CN13") (pin "27") (pinfunction "GND_27") (pintype "passive"))
      (node (ref "CN13") (pin "29") (pinfunction "GND_29") (pintype "passive"))
      (node (ref "CN13") (pin "34") (pinfunction "GND_34") (pintype "passive"))
      (node (ref "CN13") (pin "35") (pinfunction "GND_35") (pintype "passive"))
      (node (ref "CN13") (pin "37") (pinfunction "GND_37") (pintype "passive"))
      (node (ref "CN13") (pin "4") (pinfunction "GND_4") (pintype "passive"))
      (node (ref "CN13") (pin "40") (pinfunction "GND_40") (pintype "passive"))
      (node (ref "CN13") (pin "43") (pinfunction "GND_43") (pintype "passive"))
      (node (ref "CN13") (pin "50") (pinfunction "GND_50") (pintype "passive"))
      (node (ref "CN13") (pin "53") (pinfunction "GND_53") (pintype "passive"))
      (node (ref "CN13") (pin "54") (pinfunction "GND_54") (pintype "passive"))
      (node (ref "CN13") (pin "9") (pinfunction "GND_9") (pintype "passive"))
      (node (ref "CN15") (pin "A1") (pinfunction "GND1_A1") (pintype "passive"))
      (node (ref "CN15") (pin "A12") (pinfunction "GND2_A12") (pintype "passive"))
      (node (ref "CN15") (pin "B1") (pinfunction "GND3_B1") (pintype "passive"))
      (node (ref "CN15") (pin "B12") (pinfunction "GND4_B12") (pintype "passive"))
      (node (ref "CN15") (pin "SH1") (pinfunction "Shield1_SH1") (pintype "passive"))
      (node (ref "CN15") (pin "SH2") (pinfunction "Shield2_SH2") (pintype "passive"))
      (node (ref "CN15") (pin "SH3") (pinfunction "Shield3_SH3") (pintype "passive"))
      (node (ref "CN15") (pin "SH4") (pinfunction "Shield4_SH4") (pintype "passive"))
      (node (ref "Q4") (pin "2") (pinfunction "S_2") (pintype "passive"))
      (node (ref "R220") (pin "1") (pinfunction "1_1") (pintype "passive"))
      (node (ref "R231") (pin "2") (pinfunction "2_2") (pintype "passive"))
      (node (ref "R274") (pin "2") (pinfunction "2_2") (pintype "passive"))
      (node (ref "R285") (pin "1") (pinfunction "1_1") (pintype "passive"))
      (node (ref "R287") (pin "2") (pinfunction "2_2") (pintype "passive"))
      (node (ref "R327") (pin "1") (pinfunction "1_1") (pintype "passive"))
      (node (ref "R82") (pin "2") (pinfunction "2_2") (pintype "passive"))
      (node (ref "R83") (pin "2") (pinfunction "2_2") (pintype "passive"))
      (node (ref "R84") (pin "1") (pinfunction "1_1") (pintype "passive"))
      (node (ref "R85") (pin "1") (pinfunction "1_1") (pintype "passive"))
      (node (ref "TP34") (pin "1") (pinfunction "1_1") (pintype "passive"))
      (node (ref "U33") (pin "14") (pinfunction "NC6_14") (pintype "passive"))
      (node (ref "U33") (pin "15") (pinfunction "EP_15") (pintype "passive"))
      (node (ref "U33") (pin "2") (pinfunction "NC1_2") (pintype "passive"))
      (node (ref "U33") (pin "3") (pinfunction "NC2_3") (pintype "passive"))
      (node (ref "U33") (pin "4") (pinfunction "VSS_4") (pintype "passive"))
      (node (ref "U33") (pin "5") (pinfunction "NC3_5") (pintype "passive"))
      (node (ref "U33") (pin "6") (pinfunction "NC4_6") (pintype "passive"))
      (node (ref "U33") (pin "7") (pinfunction "NC5_7") (pintype "passive"))
      (node (ref "U42") (pin "4") (pinfunction "GND_4") (pintype "passive"))
      (node (ref "U43") (pin "2") (pinfunction "GND_2") (pintype "passive"))
      (node (ref "U50") (pin "12") (pinfunction "GND_12") (pintype "passive"))
      (node (ref "U50") (pin "16") (pinfunction "I2C_ADD_16") (pintype "passive"))
      (node (ref "U50") (pin "21") (pinfunction "GND_21") (pintype "passive"))
    )
    (net (code "46") (name "Net-(CN13-COEX1)") (class "Default")
      (node (ref "CN13") (pin "3") (pinfunction "COEX1_3") (pintype "passive"))
      (node (ref "TP14") (pin "1") (pinfunction "1_1") (pintype "passive"))
    )
    (net (code "47") (name "Net-(CN13-COEX2)") (class "Default")
      (node (ref "CN13") (pin "5") (pinfunction "COEX2_5") (pintype "passive"))
      (node (ref "TP15") (pin "1") (pinfunction "1_1") (pintype "passive"))
    )
    (net (code "48") (name "Net-(CN13-LED_notWLAN)") (class "Default")
      (node (ref "CN13") (pin "44") (pinfunction "LED_notWLAN_44") (pintype "passive"))
      (node (ref "LD10") (pin "2") (pintype "passive"))
    )
    (net (code "49") (name "Net-(CN13-LED_notWPAN)") (class "Default")
      (node (ref "CN13") (pin "46") (pinfunction "LED_notWPAN_46") (pintype "passive"))
      (node (ref "LED2") (pin "2") (pintype "passive"))
    )
    (net (code "50") (name "Net-(CN13-LED_notWWLAN)") (class "Default")
      (node (ref "CN13") (pin "42") (pinfunction "LED_notWWLAN_42") (pintype "passive"))
      (node (ref "TP23") (pin "1") (pinfunction "1_1") (pintype "passive"))
    )
    (net (code "51") (name "Net-(CN13-RSVD3)") (class "Default")
      (node (ref "CN13") (pin "45") (pinfunction "RSVD3_45") (pintype "passive"))
      (node (ref "CN13") (pin "47") (pinfunction "RSVD4_47") (pintype "passive"))
      (node (ref "CN13") (pin "49") (pinfunction "RSVD5_49") (pintype "passive"))
      (node (ref "TP24") (pin "1") (pinfunction "1_1") (pintype "passive"))
    )
    (net (code "52") (name "Net-(CN13-RSVD6)") (class "Default")
      (node (ref "CN13") (pin "51") (pinfunction "RSVD6_51") (pintype "passive"))
      (node (ref "TP25") (pin "1") (pinfunction "1_1") (pintype "passive"))
    )
    (net (code "53") (name "Net-(CN13-SMB_CLK)") (class "Default")
      (node (ref "CN13") (pin "30") (pinfunction "SMB_CLK_30") (pintype "passive"))
      (node (ref "R290") (pin "1") (pinfunction "1_1") (pintype "passive"))
    )
    (net (code "54") (name "Net-(CN13-SMB_DATA)") (class "Default")
      (node (ref "CN13") (pin "32") (pinfunction "SMB_DATA_32") (pintype "passive"))
      (node (ref "R291") (pin "1") (pinfunction "1_1") (pintype "passive"))
    )
    (net (code "55") (name "Net-(CN13-UIM_CLK)") (class "Default")
      (node (ref "CN13") (pin "12") (pinfunction "UIM_CLK_12") (pintype "passive"))
      (node (ref "TP19") (pin "1") (pinfunction "1_1") (pintype "passive"))
    )
    (net (code "56") (name "Net-(CN13-UIM_DATA)") (class "Default")
      (node (ref "CN13") (pin "10") (pinfunction "UIM_DATA_10") (pintype "passive"))
      (node (ref "TP17") (pin "1") (pinfunction "1_1") (pintype "passive"))
    )
    (net (code "57") (name "Net-(CN13-UIM_PWR)") (class "Default")
      (node (ref "CN13") (pin "8") (pinfunction "UIM_PWR_8") (pintype "passive"))
      (node (ref "TP16") (pin "1") (pinfunction "1_1") (pintype "passive"))
    )
    (net (code "58") (name "Net-(CN13-UIM_RESET)") (class "Default")
      (node (ref "CN13") (pin "14") (pinfunction "UIM_RESET_14") (pintype "passive"))
      (node (ref "TP18") (pin "1") (pinfunction "1_1") (pintype "passive"))
    )
    (net (code "59") (name "Net-(CN13-UIM_VPP)") (class "Default")
      (node (ref "CN13") (pin "16") (pinfunction "UIM_VPP_16") (pintype "passive"))
      (node (ref "TP20") (pin "1") (pinfunction "1_1") (pintype "passive"))
    )
    (net (code "60") (name "Net-(CN13-W_notDISABLE)") (class "Default")
      (node (ref "CN13") (pin "20") (pinfunction "W_notDISABLE_20") (pintype "passive"))
      (node (ref "TP21") (pin "1") (pinfunction "1_1") (pintype "passive"))
    )
    (net (code "61") (name "Net-(CN15-CC1)") (class "Default")
      (node (ref "C168") (pin "2") (pinfunction "2_2") (pintype "passive"))
      (node (ref "CN15") (pin "A5") (pinfunction "CC1_A5") (pintype "passive"))
      (node (ref "U50") (pin "15") (pinfunction "CC1c_15") (pintype "passive"))
    )
    (net (code "62") (name "Net-(CN15-CC2)") (class "Default")
      (node (ref "C171") (pin "2") (pinfunction "2_2") (pintype "passive"))
      (node (ref "CN15") (pin "B5") (pinfunction "CC2_B5") (pintype "passive"))
      (node (ref "U50") (pin "13") (pinfunction "CC2c_13") (pintype "passive"))
    )
    (net (code "63") (name "Net-(LD10-Pad1)") (class "Default")
      (node (ref "LD10") (pin "1") (pintype "passive"))
      (node (ref "R172") (pin "2") (pinfunction "2_2") (pintype "passive"))
    )
    (net (code "64") (name "Net-(LED2-Pad1)") (class "Default")
      (node (ref "LED2") (pin "1") (pintype "passive"))
      (node (ref "R171") (pin "1") (pinfunction "1_1") (pintype "passive"))
    )
    (net (code "65") (name "Net-(Q4-D)") (class "Default")
      (node (ref "Q4") (pin "3") (pinfunction "D_3") (pintype "passive"))
      (node (ref "U33") (pin "1") (pinfunction "OE_1") (pintype "passive"))
    )
    (net (code "66") (name "Net-(U27E-COMBOPHY_REXT)") (class "Default")
      (node (ref "R285") (pin "2") (pinfunction "2_2") (pintype "passive"))
      (node (ref "U27") (pin "Y20") (pinfunction "COMBOPHY_REXT_Y20") (pintype "passive"))
    )
    (net (code "67") (name "Net-(U27E-USB3DR_TXRTUNE)") (class "Default")
      (node (ref "R287") (pin "1") (pinfunction "1_1") (pintype "passive"))
      (node (ref "U27") (pin "V17") (pinfunction "USB3DR_TXRTUNE_V17") (pintype "passive"))
    )
    (net (code "68") (name "Net-(U27E-USBH_HS_TXRTUNE)") (class "Default")
      (node (ref "R274") (pin "1") (pinfunction "1_1") (pintype "passive"))
      (node (ref "U27") (pin "V16") (pinfunction "USBH_HS_TXRTUNE_V16") (pintype "passive"))
    )
    (net (code "69") (name "Net-(U33-VDD0)") (class "Default")
      (node (ref "C101") (pin "2") (pinfunction "2_2") (pintype "passive"))
      (node (ref "C102") (pin "2") (pinfunction "2_2") (pintype "passive"))
      (node (ref "R92") (pin "2") (pinfunction "2_2") (pintype "passive"))
      (node (ref "U33") (pin "12") (pinfunction "VDD1_12") (pintype "passive"))
      (node (ref "U33") (pin "13") (pinfunction "VDD0_13") (pintype "passive"))
    )
    (net (code "70") (name "Net-(U50-CBIAS)") (class "Default")
      (node (ref "C170") (pin "2") (pinfunction "2_2") (pintype "passive"))
      (node (ref "U50") (pin "14") (pinfunction "CBIAS_14") (pintype "passive"))
    )
    (net (code "71") (name "Net-(U50-EN)") (class "Default")
      (node (ref "R223") (pin "1") (pinfunction "1_1") (pintype "passive"))
      (node (ref "R326") (pin "2") (pinfunction "2_2") (pintype "passive"))
      (node (ref "R327") (pin "2") (pinfunction "2_2") (pintype "passive"))
      (node (ref "U50") (pin "20") (pinfunction "EN_20") (pintype "passive"))
    )
    (net (code "72") (name "Net-(U50-IANA)") (class "Default")
      (node (ref "TP38") (pin "1") (pinfunction "1_1") (pintype "passive"))
      (node (ref "U50") (pin "4") (pinfunction "IANA_4") (pintype "passive"))
    )
    (net (code "73") (name "Net-(U50-ISENSE)") (class "Default")
      (node (ref "Q5") (pin "7") (pinfunction "D2_7") (pintype "passive"))
      (node (ref "Q5") (pin "8") (pinfunction "D2_8") (pintype "passive"))
      (node (ref "R225") (pin "2") (pinfunction "2_2") (pintype "passive"))
      (node (ref "U50") (pin "10") (pinfunction "ISENSE_10") (pintype "passive"))
    )
    (net (code "74") (name "Net-(U50-VSENSE)") (class "Default")
      (node (ref "R231") (pin "1") (pinfunction "1_1") (pintype "passive"))
      (node (ref "R232") (pin "2") (pinfunction "2_2") (pintype "passive"))
      (node (ref "U50") (pin "11") (pinfunction "VSENSE_11") (pintype "passive"))
    )
    (net (code "75") (name "VDDIO") (class "Default")
      (node (ref "R223") (pin "2") (pinfunction "2_2") (pintype "passive"))
      (node (ref "R91") (pin "2") (pinfunction "2_2") (pintype "passive"))
    )
    (net (code "76") (name "unconnected-(CN13-RSVD1-Pad17)") (class "Default")
      (node (ref "CN13") (pin "17") (pinfunction "RSVD1_17") (pintype "passive+no_connect"))
    )
    (net (code "77") (name "unconnected-(CN13-RSVD2-Pad19)") (class "Default")
      (node (ref "CN13") (pin "19") (pinfunction "RSVD2_19") (pintype "passive+no_connect"))
    )
    (net (code "78") (name "unconnected-(CN15-RX1+-PadB11)") (class "Default")
      (node (ref "CN15") (pin "B11") (pinfunction "RX1+_B11") (pintype "passive+no_connect"))
    )
    (net (code "79") (name "unconnected-(CN15-RX1--PadB10)") (class "Default")
      (node (ref "CN15") (pin "B10") (pinfunction "RX1-_B10") (pintype "passive+no_connect"))
    )
    (net (code "80") (name "unconnected-(CN15-RX2+-PadA11)") (class "Default")
      (node (ref "CN15") (pin "A11") (pinfunction "RX2+_A11") (pintype "passive+no_connect"))
    )
    (net (code "81") (name "unconnected-(CN15-RX2--PadA10)") (class "Default")
      (node (ref "CN15") (pin "A10") (pinfunction "RX2-_A10") (pintype "passive+no_connect"))
    )
    (net (code "82") (name "unconnected-(CN15-SBU1-PadA8)") (class "Default")
      (node (ref "CN15") (pin "A8") (pinfunction "SBU1_A8") (pintype "passive+no_connect"))
    )
    (net (code "83") (name "unconnected-(CN15-SBU2-PadB8)") (class "Default")
      (node (ref "CN15") (pin "B8") (pinfunction "SBU2_B8") (pintype "passive+no_connect"))
    )
    (net (code "84") (name "unconnected-(CN15-TX1+-PadA2)") (class "Default")
      (node (ref "CN15") (pin "A2") (pinfunction "TX1+_A2") (pintype "passive+no_connect"))
    )
    (net (code "85") (name "unconnected-(CN15-TX1--PadA3)") (class "Default")
      (node (ref "CN15") (pin "A3") (pinfunction "TX1-_A3") (pintype "passive+no_connect"))
    )
    (net (code "86") (name "unconnected-(CN15-TX2+-PadB2)") (class "Default")
      (node (ref "CN15") (pin "B2") (pinfunction "TX2+_B2") (pintype "passive+no_connect"))
    )
    (net (code "87") (name "unconnected-(CN15-TX2--PadB3)") (class "Default")
      (node (ref "CN15") (pin "B3") (pinfunction "TX2-_B3") (pintype "passive+no_connect"))
    )
    (net (code "88") (name "unconnected-(U27E-DNC-PadU16)") (class "Default")
      (node (ref "U27") (pin "U16") (pinfunction "DNC_U16") (pintype "passive+no_connect"))
    )
    (net (code "89") (name "unconnected-(U42-GND-Pad3)") (class "Default")
      (node (ref "U42") (pin "3") (pinfunction "GND_3") (pintype "passive+no_connect"))
    )
    (net (code "90") (name "unconnected-(U50-GDCG-Pad7)") (class "Default")
      (node (ref "U50") (pin "7") (pinfunction "GDCG_7") (pintype "passive+no_connect"))
    )
    (net (code "91") (name "unconnected-(U50-GDCS-Pad8)") (class "Default")
      (node (ref "U50") (pin "8") (pinfunction "GDCS_8") (pintype "passive+no_connect"))
    )
  )
)
